# SIM868.net
KiCad netlist of a schematic drawn in Altium Designer
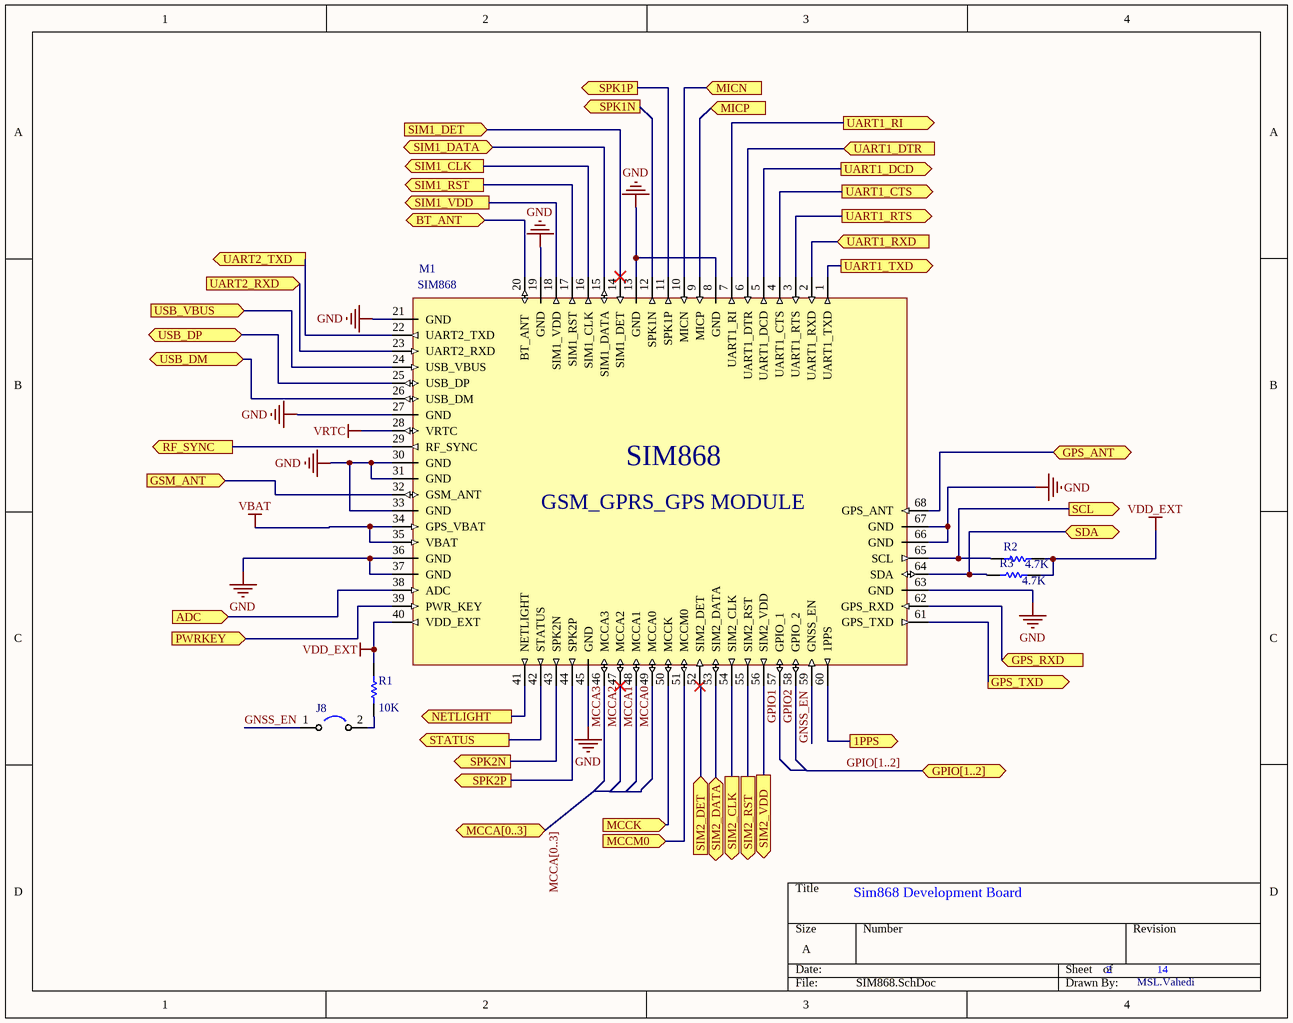
[diagram p0: SIM868.SchDoc]

(export (version "E")
  (design (tool "Eeschema 10.0.6"))
  (components
    (comp (ref "J8") (value "~") (footprint "JuMPER") (libsource (lib "Schlib1") (part "JUMPER")))
    (comp (ref "M1") (value "SIM868") (footprint "SIM868") (libsource (lib "sim868.~(10)") (part "SIM868")))
    (comp (ref "R1")
      (value "10K")
      (footprint "RES0805")
      (description "Resistor")
      (fields (field (name "PUBLISHER") "Altium Limited"))
      (libsource (lib "Miscellaneous Devices") (part "Res1"))
    )
    (comp (ref "R2")
      (value "4.7K")
      (footprint "RES0805")
      (description "Resistor")
      (fields (field (name "PUBLISHER") "Altium Limited"))
      (libsource (lib "Miscellaneous Devices") (part "Res1"))
    )
    (comp (ref "R3")
      (value "4.7K")
      (footprint "RES0805")
      (description "Resistor")
      (fields (field (name "PUBLISHER") "Altium Limited"))
      (libsource (lib "Miscellaneous Devices") (part "Res1"))
    )
  )
  (nets
    (net (code "1") (name "/1PPS") (class "Default")
      (node (ref "M1") (pin "60") (pinfunction "1PPS_60") (pintype "output"))
    )
    (net (code "2") (name "/ADC") (class "Default")
      (node (ref "M1") (pin "38") (pinfunction "ADC_38") (pintype "input"))
    )
    (net (code "3") (name "/BT_ANT") (class "Default")
      (node (ref "M1") (pin "20") (pinfunction "BT_ANT_20") (pintype "bidirectional"))
    )
    (net (code "4") (name "/GNSS_EN") (class "Default")
      (node (ref "J8") (pin "1") (pintype "passive"))
      (node (ref "M1") (pin "59") (pinfunction "GNSS_EN_59") (pintype "input"))
    )
    (net (code "5") (name "/GPIO1") (class "Default")
      (node (ref "M1") (pin "57") (pinfunction "GPIO_1_57") (pintype "bidirectional"))
    )
    (net (code "6") (name "/GPIO2") (class "Default")
      (node (ref "M1") (pin "58") (pinfunction "GPIO_2_58") (pintype "bidirectional"))
    )
    (net (code "8") (name "/GPS_ANT") (class "Default")
      (node (ref "M1") (pin "68") (pinfunction "GPS_ANT_68") (pintype "input"))
    )
    (net (code "9") (name "/GPS_RXD") (class "Default")
      (node (ref "M1") (pin "62") (pinfunction "GPS_RXD_62") (pintype "input"))
    )
    (net (code "10") (name "/GPS_TXD") (class "Default")
      (node (ref "M1") (pin "61") (pinfunction "GPS_TXD_61") (pintype "output"))
    )
    (net (code "11") (name "/GSM_ANT") (class "Default")
      (node (ref "M1") (pin "32") (pinfunction "GSM_ANT_32") (pintype "bidirectional"))
    )
    (net (code "12") (name "/MCCA0") (class "Default")
      (node (ref "M1") (pin "49") (pinfunction "MCCA0_49") (pintype "bidirectional"))
    )
    (net (code "13") (name "/MCCA1") (class "Default")
      (node (ref "M1") (pin "48") (pinfunction "MCCA1_48") (pintype "bidirectional"))
    )
    (net (code "14") (name "/MCCA2") (class "Default")
      (node (ref "M1") (pin "47") (pinfunction "MCCA2_47") (pintype "bidirectional+no_connect"))
    )
    (net (code "15") (name "/MCCA3") (class "Default")
      (node (ref "M1") (pin "46") (pinfunction "MCCA3_46") (pintype "bidirectional"))
    )
    (net (code "17") (name "/MCCK") (class "Default")
      (node (ref "M1") (pin "50") (pinfunction "MCCK_50") (pintype "bidirectional"))
    )
    (net (code "18") (name "/MCCM0") (class "Default")
      (node (ref "M1") (pin "51") (pinfunction "MCCM0_51") (pintype "bidirectional"))
    )
    (net (code "19") (name "/MICN") (class "Default")
      (node (ref "M1") (pin "10") (pinfunction "MICN_10") (pintype "input"))
    )
    (net (code "20") (name "/MICP") (class "Default")
      (node (ref "M1") (pin "9") (pinfunction "MICP_9") (pintype "input"))
    )
    (net (code "21") (name "/NETLIGHT") (class "Default")
      (node (ref "M1") (pin "41") (pinfunction "NETLIGHT_41") (pintype "output"))
    )
    (net (code "22") (name "/PWRKEY") (class "Default")
      (node (ref "M1") (pin "39") (pinfunction "PWR_KEY_39") (pintype "input"))
    )
    (net (code "23") (name "/RF_SYNC") (class "Default")
      (node (ref "M1") (pin "29") (pinfunction "RF_SYNC_29") (pintype "output"))
    )
    (net (code "24") (name "/SCL") (class "Default")
      (node (ref "M1") (pin "65") (pinfunction "SCL_65") (pintype "output"))
      (node (ref "R2") (pin "1") (pinfunction "1_1") (pintype "passive"))
    )
    (net (code "25") (name "/SDA") (class "Default")
      (node (ref "M1") (pin "64") (pinfunction "SDA_64") (pintype "bidirectional"))
      (node (ref "R3") (pin "1") (pinfunction "1_1") (pintype "passive"))
    )
    (net (code "26") (name "/SIM1_CLK") (class "Default")
      (node (ref "M1") (pin "16") (pinfunction "SIM1_CLK_16") (pintype "output"))
    )
    (net (code "27") (name "/SIM1_DATA") (class "Default")
      (node (ref "M1") (pin "15") (pinfunction "SIM1_DATA_15") (pintype "bidirectional"))
    )
    (net (code "28") (name "/SIM1_DET") (class "Default")
      (node (ref "M1") (pin "14") (pinfunction "SIM1_DET_14") (pintype "input+no_connect"))
    )
    (net (code "29") (name "/SIM1_RST") (class "Default")
      (node (ref "M1") (pin "17") (pinfunction "SIM1_RST_17") (pintype "output"))
    )
    (net (code "30") (name "/SIM1_VDD") (class "Default")
      (node (ref "M1") (pin "18") (pinfunction "SIM1_VDD_18") (pintype "output"))
    )
    (net (code "31") (name "/SIM2_CLK") (class "Default")
      (node (ref "M1") (pin "54") (pinfunction "SIM2_CLK_54") (pintype "output"))
    )
    (net (code "32") (name "/SIM2_DATA") (class "Default")
      (node (ref "M1") (pin "53") (pinfunction "SIM2_DATA_53") (pintype "bidirectional"))
    )
    (net (code "33") (name "/SIM2_DET") (class "Default")
      (node (ref "M1") (pin "52") (pinfunction "SIM2_DET_52") (pintype "input+no_connect"))
    )
    (net (code "34") (name "/SIM2_RST") (class "Default")
      (node (ref "M1") (pin "55") (pinfunction "SIM2_RST_55") (pintype "output"))
    )
    (net (code "35") (name "/SIM2_VDD") (class "Default")
      (node (ref "M1") (pin "56") (pinfunction "SIM2_VDD_56") (pintype "output"))
    )
    (net (code "36") (name "/SPK1N") (class "Default")
      (node (ref "M1") (pin "12") (pinfunction "SPK1N_12") (pintype "output"))
    )
    (net (code "37") (name "/SPK1P") (class "Default")
      (node (ref "M1") (pin "11") (pinfunction "SPK1P_11") (pintype "output"))
    )
    (net (code "38") (name "/SPK2N") (class "Default")
      (node (ref "M1") (pin "43") (pinfunction "SPK2N_43") (pintype "output"))
    )
    (net (code "39") (name "/SPK2P") (class "Default")
      (node (ref "M1") (pin "44") (pinfunction "SPK2P_44") (pintype "output"))
    )
    (net (code "40") (name "/STATUS") (class "Default")
      (node (ref "M1") (pin "42") (pinfunction "STATUS_42") (pintype "output"))
    )
    (net (code "41") (name "/UART1_CTS") (class "Default")
      (node (ref "M1") (pin "4") (pinfunction "UART1_CTS_4") (pintype "output"))
    )
    (net (code "42") (name "/UART1_DCD") (class "Default")
      (node (ref "M1") (pin "5") (pinfunction "UART1_DCD_5") (pintype "output"))
    )
    (net (code "43") (name "/UART1_DTR") (class "Default")
      (node (ref "M1") (pin "6") (pinfunction "UART1_DTR_6") (pintype "input"))
    )
    (net (code "44") (name "/UART1_RI") (class "Default")
      (node (ref "M1") (pin "7") (pinfunction "UART1_RI_7") (pintype "output"))
    )
    (net (code "45") (name "/UART1_RTS") (class "Default")
      (node (ref "M1") (pin "3") (pinfunction "UART1_RTS_3") (pintype "input"))
    )
    (net (code "46") (name "/UART1_RXD") (class "Default")
      (node (ref "M1") (pin "2") (pinfunction "UART1_RXD_2") (pintype "input"))
    )
    (net (code "47") (name "/UART1_TXD") (class "Default")
      (node (ref "M1") (pin "1") (pinfunction "UART1_TXD_1") (pintype "output"))
    )
    (net (code "48") (name "/UART2_RXD") (class "Default")
      (node (ref "M1") (pin "23") (pinfunction "UART2_RXD_23") (pintype "input"))
    )
    (net (code "49") (name "/UART2_TXD") (class "Default")
      (node (ref "M1") (pin "22") (pinfunction "UART2_TXD_22") (pintype "output"))
    )
    (net (code "50") (name "/USB_DM") (class "Default")
      (node (ref "M1") (pin "26") (pinfunction "USB_DM_26") (pintype "bidirectional"))
    )
    (net (code "51") (name "/USB_DP") (class "Default")
      (node (ref "M1") (pin "25") (pinfunction "USB_DP_25") (pintype "bidirectional"))
    )
    (net (code "52") (name "/USB_VBUS") (class "Default")
      (node (ref "M1") (pin "24") (pinfunction "USB_VBUS_24") (pintype "input"))
    )
    (net (code "53") (name "GND") (class "Default")
      (node (ref "M1") (pin "13") (pinfunction "GND_13") (pintype "power_in"))
      (node (ref "M1") (pin "19") (pinfunction "GND_19") (pintype "power_in"))
      (node (ref "M1") (pin "21") (pinfunction "GND_21") (pintype "power_in"))
      (node (ref "M1") (pin "27") (pinfunction "GND_27") (pintype "power_in"))
      (node (ref "M1") (pin "30") (pinfunction "GND_30") (pintype "power_in"))
      (node (ref "M1") (pin "31") (pinfunction "GND_31") (pintype "power_in"))
      (node (ref "M1") (pin "33") (pinfunction "GND_33") (pintype "power_in"))
      (node (ref "M1") (pin "36") (pinfunction "GND_36") (pintype "power_in"))
      (node (ref "M1") (pin "37") (pinfunction "GND_37") (pintype "power_in"))
      (node (ref "M1") (pin "45") (pinfunction "GND_45") (pintype "power_in"))
      (node (ref "M1") (pin "63") (pinfunction "GND_63") (pintype "power_in"))
      (node (ref "M1") (pin "66") (pinfunction "GND_66") (pintype "power_in"))
      (node (ref "M1") (pin "67") (pinfunction "GND_67") (pintype "power_in"))
      (node (ref "M1") (pin "8") (pinfunction "GND_8") (pintype "power_in"))
    )
    (net (code "54") (name "Net-(J8-Pad2)") (class "Default")
      (node (ref "J8") (pin "2") (pintype "passive"))
      (node (ref "R1") (pin "1") (pinfunction "1_1") (pintype "passive"))
    )
    (net (code "55") (name "VBAT") (class "Default")
      (node (ref "M1") (pin "34") (pinfunction "GPS_VBAT_34") (pintype "input"))
      (node (ref "M1") (pin "35") (pinfunction "VBAT_35") (pintype "input"))
    )
    (net (code "56") (name "VDD_EXT") (class "Default")
      (node (ref "M1") (pin "40") (pinfunction "VDD_EXT_40") (pintype "output"))
      (node (ref "R1") (pin "2") (pinfunction "2_2") (pintype "passive"))
      (node (ref "R2") (pin "2") (pinfunction "2_2") (pintype "passive"))
      (node (ref "R3") (pin "2") (pinfunction "2_2") (pintype "passive"))
    )
    (net (code "57") (name "VRTC") (class "Default")
      (node (ref "M1") (pin "28") (pinfunction "VRTC_28") (pintype "bidirectional"))
    )
  )
)
